# tm8_XP2.net
KiCad netlist of a schematic drawn in EAGLE
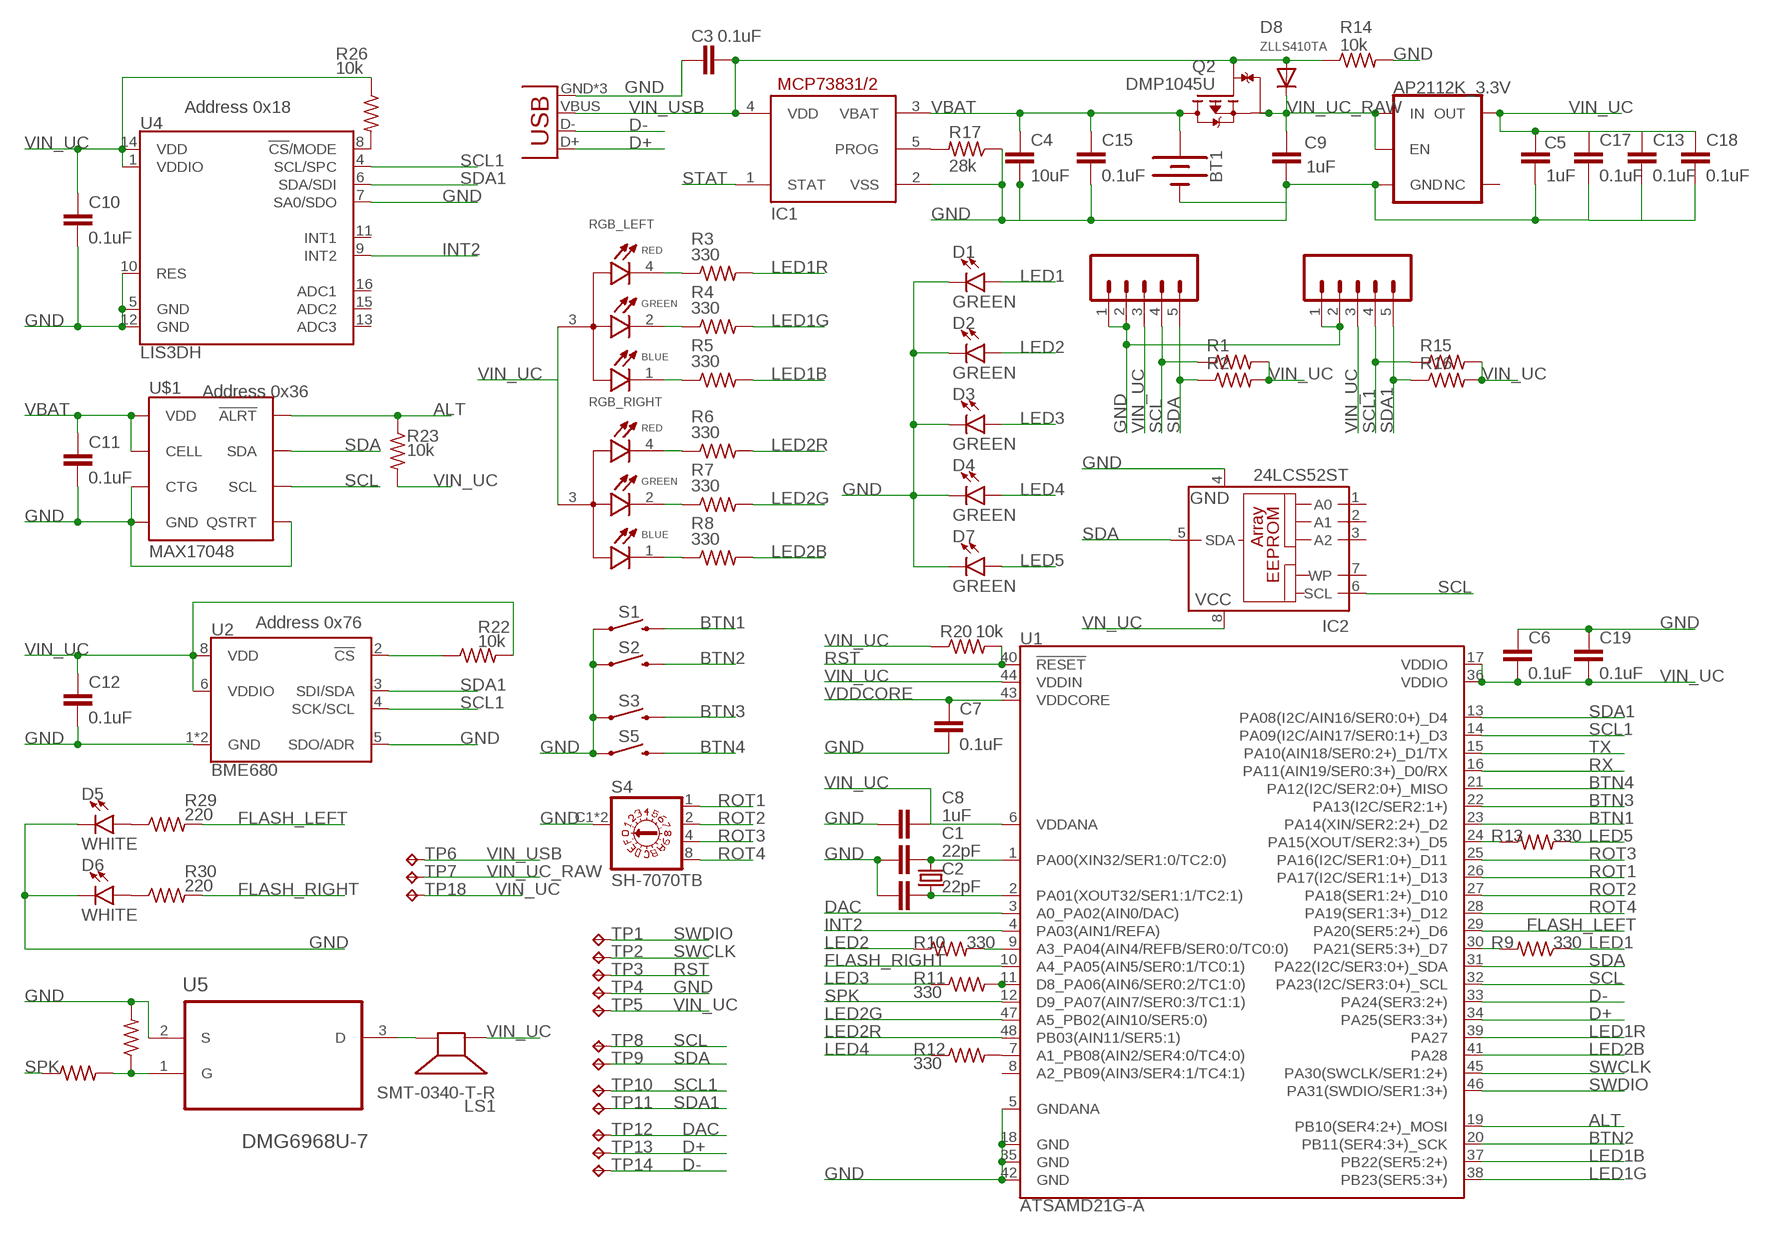
[diagram p0: schematic, sheet 1]

(export (version "E")
  (design (tool "Eeschema 10.0.6"))
  (components
    (comp (ref "AP2112K_3.3V")
      (value "3.3V")
      (footprint "eagle-import:SOT23-5")
      (libsource (lib "eagle-import") (part "V_REG_AP2112K-3.3V"))
    )
    (comp (ref "BT1")
      (value "BATTERY-20MM_SMD_4LEGS_OVERPASTE_INNER")
      (footprint "eagle-import:BATTCON_20MM_4LEGS_OVERPASTE_INNER")
      (libsource (lib "eagle-import") (part "BATTERY-20MM_SMD_4LEGS_OVERPASTE_INNER"))
    )
    (comp (ref "C1")
      (value "22pF")
      (footprint "eagle-import:C0402")
      (libsource (lib "eagle-import") (part "C-EUC0402"))
    )
    (comp (ref "C2")
      (value "22pF")
      (footprint "eagle-import:C0402")
      (libsource (lib "eagle-import") (part "C-EUC0402"))
    )
    (comp (ref "C3")
      (value "0.1uF")
      (footprint "eagle-import:C0402")
      (libsource (lib "eagle-import") (part "C-EUC0402"))
    )
    (comp (ref "C4")
      (value "10uF")
      (footprint "eagle-import:C0402")
      (libsource (lib "eagle-import") (part "C-EUC0402"))
    )
    (comp (ref "C5")
      (value "1uF")
      (footprint "eagle-import:C0402")
      (libsource (lib "eagle-import") (part "C-EUC0402"))
    )
    (comp (ref "C6")
      (value "0.1uF")
      (footprint "eagle-import:C0402")
      (libsource (lib "eagle-import") (part "C-EUC0402"))
    )
    (comp (ref "C7")
      (value "0.1uF")
      (footprint "eagle-import:C0402")
      (libsource (lib "eagle-import") (part "C-EUC0402"))
    )
    (comp (ref "C8")
      (value "1uF")
      (footprint "eagle-import:C0402")
      (libsource (lib "eagle-import") (part "C-EUC0402"))
    )
    (comp (ref "C9")
      (value "1uF")
      (footprint "eagle-import:C0402")
      (libsource (lib "eagle-import") (part "C-EUC0402"))
    )
    (comp (ref "C10")
      (value "0.1uF")
      (footprint "eagle-import:C0402")
      (libsource (lib "eagle-import") (part "C-EUC0402"))
    )
    (comp (ref "C11")
      (value "0.1uF")
      (footprint "eagle-import:C0402")
      (libsource (lib "eagle-import") (part "C-EUC0402"))
    )
    (comp (ref "C12")
      (value "0.1uF")
      (footprint "eagle-import:C0402")
      (libsource (lib "eagle-import") (part "C-EUC0402"))
    )
    (comp (ref "C13")
      (value "0.1uF")
      (footprint "eagle-import:C0402")
      (libsource (lib "eagle-import") (part "C-EUC0402"))
    )
    (comp (ref "C15")
      (value "0.1uF")
      (footprint "eagle-import:C0402")
      (libsource (lib "eagle-import") (part "C-EUC0402"))
    )
    (comp (ref "C17")
      (value "0.1uF")
      (footprint "eagle-import:C0402")
      (libsource (lib "eagle-import") (part "C-EUC0402"))
    )
    (comp (ref "C18")
      (value "0.1uF")
      (footprint "eagle-import:C0402")
      (libsource (lib "eagle-import") (part "C-EUC0402"))
    )
    (comp (ref "C19")
      (value "0.1uF")
      (footprint "eagle-import:C0402")
      (libsource (lib "eagle-import") (part "C-EUC0402"))
    )
    (comp (ref "D1")
      (value "GREEN")
      (footprint "eagle-import:LED-1206")
      (libsource (lib "eagle-import") (part "LED-GREEN1206"))
    )
    (comp (ref "D2")
      (value "GREEN")
      (footprint "eagle-import:LED-1206")
      (libsource (lib "eagle-import") (part "LED-GREEN1206"))
    )
    (comp (ref "D3")
      (value "GREEN")
      (footprint "eagle-import:LED-1206")
      (libsource (lib "eagle-import") (part "LED-GREEN1206"))
    )
    (comp (ref "D4")
      (value "GREEN")
      (footprint "eagle-import:LED-1206")
      (libsource (lib "eagle-import") (part "LED-GREEN1206"))
    )
    (comp (ref "D5")
      (value "WHITE")
      (footprint "eagle-import:LED-1206")
      (libsource (lib "eagle-import") (part "LED-WHITE1206"))
    )
    (comp (ref "D6")
      (value "WHITE")
      (footprint "eagle-import:LED-1206")
      (libsource (lib "eagle-import") (part "LED-WHITE1206"))
    )
    (comp (ref "D7")
      (value "GREEN")
      (footprint "eagle-import:LED-1206")
      (libsource (lib "eagle-import") (part "LED-GREEN1206"))
    )
    (comp (ref "D8")
      (value "ZLLS410TA")
      (footprint "eagle-import:SOD-323F")
      (libsource (lib "eagle-import") (part "DIODESOD-323F"))
    )
    (comp (ref "IC1")
      (value "MCP73831/OT")
      (footprint "eagle-import:SOT23-5L")
      (libsource (lib "eagle-import") (part "MCP73831/OT"))
    )
    (comp (ref "IC2")
      (value "24LCS52ST")
      (footprint "eagle-import:TSSOP8")
      (fields (field (name "MF") "MICROCHIP") (field (name "MPN") "24LCS52T/ST"))
      (libsource (lib "eagle-import") (part "24STLCS52"))
    )
    (comp (ref "JP2")
      (value "USB-MICROB")
      (footprint "eagle-import:USB-MICROB")
      (libsource (lib "eagle-import") (part "USB-MICROB"))
    )
    (comp (ref "LCD1")
      (value "CONN_05VERT_FEMALE_HEADER")
      (footprint "eagle-import:1X05_SMD_VERTICAL_COMBO")
      (libsource (lib "eagle-import") (part "CONN_05VERT_FEMALE_HEADER"))
    )
    (comp (ref "LCD2")
      (value "CONN_05VERT_FEMALE_HEADER")
      (footprint "eagle-import:1X05_SMD_VERTICAL_COMBO")
      (libsource (lib "eagle-import") (part "CONN_05VERT_FEMALE_HEADER"))
    )
    (comp (ref "LS1")
      (value "SMT-0340-T-R")
      (footprint "eagle-import:XDCR_SMT-0340-T-R")
      (fields (field (name "MANUFACTURER") "Pui Audio"))
      (libsource (lib "eagle-import") (part "SMT-0340-T-R"))
    )
    (comp (ref "Q2")
      (value "DMP1045U")
      (footprint "eagle-import:SOT91P240X110-3N")
      (fields (field (name "MF") "Diodes Inc."))
      (libsource (lib "eagle-import") (part "DMP1045U"))
    )
    (comp (ref "R1")
      (value "R-US_R0402")
      (footprint "eagle-import:R0402")
      (libsource (lib "eagle-import") (part "adafruit_25768682_R-US_R0402"))
    )
    (comp (ref "R2")
      (value "R-US_R0402")
      (footprint "eagle-import:R0402")
      (libsource (lib "eagle-import") (part "adafruit_25768682_R-US_R0402"))
    )
    (comp (ref "R3")
      (value "330")
      (footprint "eagle-import:R0402")
      (libsource (lib "eagle-import") (part "rcl_334_R-US_R0402"))
    )
    (comp (ref "R4")
      (value "330")
      (footprint "eagle-import:R0402")
      (libsource (lib "eagle-import") (part "rcl_334_R-US_R0402"))
    )
    (comp (ref "R5")
      (value "330")
      (footprint "eagle-import:R0402")
      (libsource (lib "eagle-import") (part "rcl_334_R-US_R0402"))
    )
    (comp (ref "R6")
      (value "330")
      (footprint "eagle-import:R0402")
      (libsource (lib "eagle-import") (part "rcl_334_R-US_R0402"))
    )
    (comp (ref "R7")
      (value "330")
      (footprint "eagle-import:R0402")
      (libsource (lib "eagle-import") (part "rcl_334_R-US_R0402"))
    )
    (comp (ref "R8")
      (value "330")
      (footprint "eagle-import:R0402")
      (libsource (lib "eagle-import") (part "rcl_334_R-US_R0402"))
    )
    (comp (ref "R9")
      (value "330")
      (footprint "eagle-import:R0402")
      (libsource (lib "eagle-import") (part "rcl_334_R-US_R0402"))
    )
    (comp (ref "R10")
      (value "330")
      (footprint "eagle-import:R0402")
      (libsource (lib "eagle-import") (part "rcl_334_R-US_R0402"))
    )
    (comp (ref "R11")
      (value "330")
      (footprint "eagle-import:R0402")
      (libsource (lib "eagle-import") (part "rcl_334_R-US_R0402"))
    )
    (comp (ref "R12")
      (value "330")
      (footprint "eagle-import:R0402")
      (libsource (lib "eagle-import") (part "rcl_334_R-US_R0402"))
    )
    (comp (ref "R13")
      (value "330")
      (footprint "eagle-import:R0402")
      (libsource (lib "eagle-import") (part "rcl_334_R-US_R0402"))
    )
    (comp (ref "R14")
      (value "10k")
      (footprint "eagle-import:R0402")
      (libsource (lib "eagle-import") (part "R-US_R0402"))
    )
    (comp (ref "R15")
      (value "R-US_R0402")
      (footprint "eagle-import:R0402")
      (libsource (lib "eagle-import") (part "adafruit_25768682_R-US_R0402"))
    )
    (comp (ref "R16")
      (value "R-US_R0402")
      (footprint "eagle-import:R0402")
      (libsource (lib "eagle-import") (part "adafruit_25768682_R-US_R0402"))
    )
    (comp (ref "R17")
      (value "28k")
      (footprint "eagle-import:R0402")
      (libsource (lib "eagle-import") (part "adafruit_25768682_R-US_R0402"))
    )
    (comp (ref "R18")
      (value "220")
      (footprint "eagle-import:R0402")
      (libsource (lib "eagle-import") (part "rcl_334_R-US_R0402"))
    )
    (comp (ref "R19")
      (value "220")
      (footprint "eagle-import:R0402")
      (libsource (lib "eagle-import") (part "rcl_334_R-US_R0402"))
    )
    (comp (ref "R20")
      (value "10k")
      (footprint "eagle-import:R0402")
      (libsource (lib "eagle-import") (part "adafruit_25768682_R-US_R0402"))
    )
    (comp (ref "R22")
      (value "10k")
      (footprint "eagle-import:R0402")
      (libsource (lib "eagle-import") (part "rcl_334_R-US_R0402"))
    )
    (comp (ref "R23")
      (value "10k")
      (footprint "eagle-import:R0402")
      (libsource (lib "eagle-import") (part "rcl_334_R-US_R0402"))
    )
    (comp (ref "R26")
      (value "10k")
      (footprint "eagle-import:R0402")
      (libsource (lib "eagle-import") (part "rcl_334_R-US_R0402"))
    )
    (comp (ref "R29")
      (value "220")
      (footprint "eagle-import:R0402")
      (libsource (lib "eagle-import") (part "rcl_334_R-US_R0402"))
    )
    (comp (ref "R30")
      (value "220")
      (footprint "eagle-import:R0402")
      (libsource (lib "eagle-import") (part "rcl_334_R-US_R0402"))
    )
    (comp (ref "RGB_LEFT")
      (value "EAST1616RGBA3")
      (footprint "eagle-import:LED_EAST1616RGBA3")
      (fields (field (name "MF") "Everlight Electronics"))
      (libsource (lib "eagle-import") (part "EAST1616RGBA3"))
    )
    (comp (ref "RGB_RIGHT")
      (value "EAST1616RGBA3")
      (footprint "eagle-import:LED_EAST1616RGBA3")
      (fields (field (name "MF") "Everlight Electronics"))
      (libsource (lib "eagle-import") (part "EAST1616RGBA3"))
    )
    (comp (ref "S1")
      (value "MOMENTARY-SWITCH-SPST-SMD-6.0X3.5MM")
      (footprint "eagle-import:TACTILE_SWITCH_SMD_6.0X3.5MM")
      (libsource (lib "eagle-import") (part "MOMENTARY-SWITCH-SPST-SMD-6.0X3.5MM"))
    )
    (comp (ref "S2")
      (value "MOMENTARY-SWITCH-SPST-SMD-6.0X3.5MM")
      (footprint "eagle-import:TACTILE_SWITCH_SMD_6.0X3.5MM")
      (libsource (lib "eagle-import") (part "MOMENTARY-SWITCH-SPST-SMD-6.0X3.5MM"))
    )
    (comp (ref "S3")
      (value "MOMENTARY-SWITCH-SPST-SMD-6.0X3.5MM")
      (footprint "eagle-import:TACTILE_SWITCH_SMD_6.0X3.5MM")
      (libsource (lib "eagle-import") (part "MOMENTARY-SWITCH-SPST-SMD-6.0X3.5MM"))
    )
    (comp (ref "S4")
      (value "SH-7070TB")
      (footprint "eagle-import:SH-7070B")
      (fields (field (name "MF") "Nidec Copal"))
      (libsource (lib "eagle-import") (part "SH-7070TB"))
    )
    (comp (ref "S5")
      (value "MOMENTARY-SWITCH-SPST-SMD-6.0X3.5MM")
      (footprint "eagle-import:TACTILE_SWITCH_SMD_6.0X3.5MM")
      (libsource (lib "eagle-import") (part "MOMENTARY-SWITCH-SPST-SMD-6.0X3.5MM"))
    )
    (comp (ref "TP1")
      (value "TPTP14R")
      (footprint "eagle-import:TP14R")
      (libsource (lib "eagle-import") (part "TPTP14R"))
    )
    (comp (ref "TP2")
      (value "TPTP14R")
      (footprint "eagle-import:TP14R")
      (libsource (lib "eagle-import") (part "TPTP14R"))
    )
    (comp (ref "TP3")
      (value "TPTP14R")
      (footprint "eagle-import:TP14R")
      (libsource (lib "eagle-import") (part "TPTP14R"))
    )
    (comp (ref "TP4")
      (value "TPTP14R")
      (footprint "eagle-import:TP14R")
      (libsource (lib "eagle-import") (part "TPTP14R"))
    )
    (comp (ref "TP5")
      (value "TPTP14R")
      (footprint "eagle-import:TP14R")
      (libsource (lib "eagle-import") (part "TPTP14R"))
    )
    (comp (ref "TP6")
      (value "TPTP14R")
      (footprint "eagle-import:TP14R")
      (libsource (lib "eagle-import") (part "TPTP14R"))
    )
    (comp (ref "TP7")
      (value "TPTP14R")
      (footprint "eagle-import:TP14R")
      (libsource (lib "eagle-import") (part "TPTP14R"))
    )
    (comp (ref "TP8")
      (value "TPTP14R")
      (footprint "eagle-import:TP14R")
      (libsource (lib "eagle-import") (part "TPTP14R"))
    )
    (comp (ref "TP9")
      (value "TPTP14R")
      (footprint "eagle-import:TP14R")
      (libsource (lib "eagle-import") (part "TPTP14R"))
    )
    (comp (ref "TP10")
      (value "TPTP14R")
      (footprint "eagle-import:TP14R")
      (libsource (lib "eagle-import") (part "TPTP14R"))
    )
    (comp (ref "TP11")
      (value "TPTP14R")
      (footprint "eagle-import:TP14R")
      (libsource (lib "eagle-import") (part "TPTP14R"))
    )
    (comp (ref "TP12")
      (value "TPTP14R")
      (footprint "eagle-import:TP14R")
      (libsource (lib "eagle-import") (part "TPTP14R"))
    )
    (comp (ref "TP13")
      (value "TPTP14R")
      (footprint "eagle-import:TP14R")
      (libsource (lib "eagle-import") (part "TPTP14R"))
    )
    (comp (ref "TP14")
      (value "TPTP14R")
      (footprint "eagle-import:TP14R")
      (libsource (lib "eagle-import") (part "TPTP14R"))
    )
    (comp (ref "TP18")
      (value "TPTP14R")
      (footprint "eagle-import:TP14R")
      (libsource (lib "eagle-import") (part "TPTP14R"))
    )
    (comp (ref "U$1")
      (value "MAX17048")
      (footprint "eagle-import:DFN-8")
      (libsource (lib "eagle-import") (part "MAX17048DFN8"))
    )
    (comp (ref "U1")
      (value "ATSAMD21G-A")
      (footprint "eagle-import:TQFP-48")
      (libsource (lib "eagle-import") (part "ATSAMD21G-A"))
    )
    (comp (ref "U2")
      (value "BME680")
      (footprint "eagle-import:LGA3.0X3.0")
      (libsource (lib "eagle-import") (part "BME680-LGA"))
    )
    (comp (ref "U4")
      (value "LIS3DH")
      (footprint "eagle-import:LGA-16-3X3")
      (libsource (lib "eagle-import") (part "LIS3DH"))
    )
    (comp (ref "U5")
      (value "DMG6968U-7")
      (footprint "eagle-import:SOT95P240X110-3N")
      (fields (field (name "MF") "Diodes Inc."))
      (libsource (lib "eagle-import") (part "DMG6968U-7"))
    )
    (comp (ref "Y1")
      (value "32.768kHz")
      (footprint "eagle-import:CRYSTAL-SMD-3.2X1.5MM")
      (libsource (lib "eagle-import") (part "CRYSTAL-32.768KHZSMD-3.2X1.5"))
    )
  )
  (nets
    (net (code "1") (name "/ALT") (class "Default")
      (node (ref "R23") (pin "1") (pinfunction "1_1") (pintype "passive"))
      (node (ref "U$1") (pin "P$5") (pinfunction "~{ALRT}_P$5") (pintype "bidirectional"))
      (node (ref "U1") (pin "19") (pinfunction "PB10(SER4:2+)_MOSI_19") (pintype "bidirectional"))
    )
    (net (code "2") (name "/BTN1") (class "Default")
      (node (ref "S1") (pin "2") (pinfunction "2_2") (pintype "passive"))
      (node (ref "U1") (pin "23") (pinfunction "PA14(XIN/SER2:2+)_D2_23") (pintype "bidirectional"))
    )
    (net (code "3") (name "/BTN2") (class "Default")
      (node (ref "S2") (pin "2") (pinfunction "2_2") (pintype "passive"))
      (node (ref "U1") (pin "20") (pinfunction "PB11(SER4:3+)_SCK_20") (pintype "bidirectional"))
    )
    (net (code "4") (name "/BTN3") (class "Default")
      (node (ref "S3") (pin "2") (pinfunction "2_2") (pintype "passive"))
      (node (ref "U1") (pin "22") (pinfunction "PA13(I2C/SER2:1+)_22") (pintype "bidirectional"))
    )
    (net (code "5") (name "/BTN4") (class "Default")
      (node (ref "S5") (pin "2") (pinfunction "2_2") (pintype "passive"))
      (node (ref "U1") (pin "21") (pinfunction "PA12(I2C/SER2:0+)_MISO_21") (pintype "bidirectional"))
    )
    (net (code "6") (name "/D+") (class "Default")
      (node (ref "JP2") (pin "D+") (pinfunction "D+_D+") (pintype "bidirectional"))
      (node (ref "TP13") (pin "TP") (pinfunction "TP_TP") (pintype "input"))
      (node (ref "U1") (pin "34") (pinfunction "PA25(SER3:3+)_34") (pintype "bidirectional"))
    )
    (net (code "7") (name "/D-") (class "Default")
      (node (ref "JP2") (pin "D-") (pinfunction "D-_D-") (pintype "bidirectional"))
      (node (ref "TP14") (pin "TP") (pinfunction "TP_TP") (pintype "input"))
      (node (ref "U1") (pin "33") (pinfunction "PA24(SER3:2+)_33") (pintype "bidirectional"))
    )
    (net (code "8") (name "/DAC") (class "Default")
      (node (ref "TP12") (pin "TP") (pinfunction "TP_TP") (pintype "input"))
      (node (ref "U1") (pin "3") (pinfunction "A0_PA02(AIN0/DAC)_3") (pintype "bidirectional"))
    )
    (net (code "9") (name "/FLASH_LEFT") (class "Default")
      (node (ref "R29") (pin "2") (pinfunction "2_2") (pintype "passive"))
      (node (ref "U1") (pin "29") (pinfunction "PA20(SER5:2+)_D6_29") (pintype "bidirectional"))
    )
    (net (code "10") (name "/FLASH_RIGHT") (class "Default")
      (node (ref "R30") (pin "2") (pinfunction "2_2") (pintype "passive"))
      (node (ref "U1") (pin "10") (pinfunction "A4_PA05(AIN5/SER0:1/TC0:1)_10") (pintype "bidirectional"))
    )
    (net (code "11") (name "/GND") (class "Default")
      (node (ref "AP2112K_3.3V") (pin "2") (pinfunction "GND_2") (pintype "input"))
      (node (ref "BT1") (pin "2") (pinfunction "-_2") (pintype "power_in"))
      (node (ref "C1") (pin "1") (pinfunction "1_1") (pintype "passive"))
      (node (ref "C10") (pin "2") (pinfunction "2_2") (pintype "passive"))
      (node (ref "C11") (pin "2") (pinfunction "2_2") (pintype "passive"))
      (node (ref "C12") (pin "2") (pinfunction "2_2") (pintype "passive"))
      (node (ref "C13") (pin "2") (pinfunction "2_2") (pintype "passive"))
      (node (ref "C15") (pin "2") (pinfunction "2_2") (pintype "passive"))
      (node (ref "C17") (pin "2") (pinfunction "2_2") (pintype "passive"))
      (node (ref "C18") (pin "2") (pinfunction "2_2") (pintype "passive"))
      (node (ref "C19") (pin "1") (pinfunction "1_1") (pintype "passive"))
      (node (ref "C2") (pin "1") (pinfunction "1_1") (pintype "passive"))
      (node (ref "C3") (pin "1") (pinfunction "1_1") (pintype "passive"))
      (node (ref "C4") (pin "2") (pinfunction "2_2") (pintype "passive"))
      (node (ref "C5") (pin "2") (pinfunction "2_2") (pintype "passive"))
      (node (ref "C6") (pin "1") (pinfunction "1_1") (pintype "passive"))
      (node (ref "C7") (pin "2") (pinfunction "2_2") (pintype "passive"))
      (node (ref "C8") (pin "1") (pinfunction "1_1") (pintype "passive"))
      (node (ref "C9") (pin "2") (pinfunction "2_2") (pintype "passive"))
      (node (ref "D1") (pin "C") (pinfunction "C_C") (pintype "passive"))
      (node (ref "D2") (pin "C") (pinfunction "C_C") (pintype "passive"))
      (node (ref "D3") (pin "C") (pinfunction "C_C") (pintype "passive"))
      (node (ref "D4") (pin "C") (pinfunction "C_C") (pintype "passive"))
      (node (ref "D5") (pin "C") (pinfunction "C_C") (pintype "passive"))
      (node (ref "D6") (pin "C") (pinfunction "C_C") (pintype "passive"))
      (node (ref "D7") (pin "C") (pinfunction "C_C") (pintype "passive"))
      (node (ref "IC1") (pin "2") (pinfunction "VSS_2") (pintype "power_in"))
      (node (ref "IC2") (pin "4") (pinfunction "GND_4") (pintype "power_in"))
      (node (ref "JP2") (pin "GND") (pinfunction "GND_GND") (pintype "bidirectional"))
      (node (ref "JP2") (pin "MT1") (pinfunction "GND_MT1") (pintype "bidirectional"))
      (node (ref "JP2") (pin "MT2") (pinfunction "GND_MT2") (pintype "bidirectional"))
      (node (ref "LCD1") (pin "1") (pinfunction "1_1") (pintype "passive"))
      (node (ref "LCD1") (pin "2") (pinfunction "2_2") (pintype "passive"))
      (node (ref "LCD2") (pin "1") (pinfunction "1_1") (pintype "passive"))
      (node (ref "LCD2") (pin "2") (pinfunction "2_2") (pintype "passive"))
      (node (ref "R14") (pin "2") (pinfunction "2_2") (pintype "passive"))
      (node (ref "R17") (pin "1") (pinfunction "1_1") (pintype "passive"))
      (node (ref "R19") (pin "2") (pinfunction "2_2") (pintype "passive"))
      (node (ref "S1") (pin "1") (pinfunction "1_1") (pintype "passive"))
      (node (ref "S2") (pin "1") (pinfunction "1_1") (pintype "passive"))
      (node (ref "S3") (pin "1") (pinfunction "1_1") (pintype "passive"))
      (node (ref "S4") (pin "C1") (pinfunction "C_C1") (pintype "passive"))
      (node (ref "S4") (pin "C2") (pinfunction "C_C2") (pintype "passive"))
      (node (ref "S5") (pin "1") (pinfunction "1_1") (pintype "passive"))
      (node (ref "TP4") (pin "TP") (pinfunction "TP_TP") (pintype "input"))
      (node (ref "U$1") (pin "P$1") (pinfunction "CTG_P$1") (pintype "input"))
      (node (ref "U$1") (pin "P$4") (pinfunction "GND_P$4") (pintype "bidirectional"))
      (node (ref "U$1") (pin "P$6") (pinfunction "QSTRT_P$6") (pintype "bidirectional"))
      (node (ref "U$1") (pin "P$9") (pinfunction "GND_P$9") (pintype "bidirectional"))
      (node (ref "U1") (pin "18") (pinfunction "GND_18") (pintype "bidirectional"))
      (node (ref "U1") (pin "35") (pinfunction "GND_35") (pintype "bidirectional"))
      (node (ref "U1") (pin "42") (pinfunction "GND_42") (pintype "bidirectional"))
      (node (ref "U1") (pin "5") (pinfunction "GNDANA_5") (pintype "bidirectional"))
      (node (ref "U2") (pin "1") (pinfunction "GND_1") (pintype "bidirectional"))
      (node (ref "U2") (pin "5") (pinfunction "SDO/ADR_5") (pintype "bidirectional"))
      (node (ref "U2") (pin "7") (pinfunction "GND_7") (pintype "bidirectional"))
      (node (ref "U4") (pin "10") (pinfunction "RES_10") (pintype "bidirectional"))
      (node (ref "U4") (pin "12") (pinfunction "GND_12") (pintype "bidirectional"))
      (node (ref "U4") (pin "5") (pinfunction "GND_5") (pintype "bidirectional"))
      (node (ref "U4") (pin "7") (pinfunction "SA0/SDO_7") (pintype "bidirectional"))
      (node (ref "U5") (pin "2") (pinfunction "S_2") (pintype "passive"))
    )
    (net (code "12") (name "/INT2") (class "Default")
      (node (ref "U1") (pin "4") (pinfunction "PA03(AIN1/REFA)_4") (pintype "bidirectional"))
      (node (ref "U4") (pin "9") (pinfunction "INT2_9") (pintype "bidirectional"))
    )
    (net (code "13") (name "/LED1") (class "Default")
      (node (ref "D1") (pin "A") (pinfunction "A_A") (pintype "passive"))
      (node (ref "R9") (pin "1") (pinfunction "1_1") (pintype "passive"))
    )
    (net (code "14") (name "/LED1B") (class "Default")
      (node (ref "R5") (pin "2") (pinfunction "2_2") (pintype "passive"))
      (node (ref "U1") (pin "37") (pinfunction "PB22(SER5:2+)_37") (pintype "bidirectional"))
    )
    (net (code "15") (name "/LED1G") (class "Default")
      (node (ref "R4") (pin "2") (pinfunction "2_2") (pintype "passive"))
      (node (ref "U1") (pin "38") (pinfunction "PB23(SER5:3+)_38") (pintype "bidirectional"))
    )
    (net (code "16") (name "/LED1R") (class "Default")
      (node (ref "R3") (pin "2") (pinfunction "2_2") (pintype "passive"))
      (node (ref "U1") (pin "39") (pinfunction "PA27_39") (pintype "bidirectional"))
    )
    (net (code "17") (name "/LED2") (class "Default")
      (node (ref "D2") (pin "A") (pinfunction "A_A") (pintype "passive"))
      (node (ref "R10") (pin "1") (pinfunction "1_1") (pintype "passive"))
    )
    (net (code "18") (name "/LED2B") (class "Default")
      (node (ref "R8") (pin "2") (pinfunction "2_2") (pintype "passive"))
      (node (ref "U1") (pin "41") (pinfunction "PA28_41") (pintype "bidirectional"))
    )
    (net (code "19") (name "/LED2G") (class "Default")
      (node (ref "R7") (pin "2") (pinfunction "2_2") (pintype "passive"))
      (node (ref "U1") (pin "47") (pinfunction "A5_PB02(AIN10/SER5:0)_47") (pintype "bidirectional"))
    )
    (net (code "20") (name "/LED2R") (class "Default")
      (node (ref "R6") (pin "2") (pinfunction "2_2") (pintype "passive"))
      (node (ref "U1") (pin "48") (pinfunction "PB03(AIN11/SER5:1)_48") (pintype "bidirectional"))
    )
    (net (code "21") (name "/LED3") (class "Default")
      (node (ref "D3") (pin "A") (pinfunction "A_A") (pintype "passive"))
      (node (ref "R11") (pin "1") (pinfunction "1_1") (pintype "passive"))
    )
    (net (code "22") (name "/LED4") (class "Default")
      (node (ref "D4") (pin "A") (pinfunction "A_A") (pintype "passive"))
      (node (ref "R12") (pin "1") (pinfunction "1_1") (pintype "passive"))
    )
    (net (code "23") (name "/LED5") (class "Default")
      (node (ref "D7") (pin "A") (pinfunction "A_A") (pintype "passive"))
      (node (ref "R13") (pin "2") (pinfunction "2_2") (pintype "passive"))
    )
    (net (code "24") (name "/ROT1") (class "Default")
      (node (ref "S4") (pin "1") (pinfunction "1_1") (pintype "passive"))
      (node (ref "U1") (pin "26") (pinfunction "PA17(I2C/SER1:1+)_D13_26") (pintype "bidirectional"))
    )
    (net (code "25") (name "/ROT2") (class "Default")
      (node (ref "S4") (pin "2") (pinfunction "2_2") (pintype "passive"))
      (node (ref "U1") (pin "27") (pinfunction "PA18(SER1:2+)_D10_27") (pintype "bidirectional"))
    )
    (net (code "26") (name "/ROT3") (class "Default")
      (node (ref "S4") (pin "4") (pinfunction "4_4") (pintype "passive"))
      (node (ref "U1") (pin "25") (pinfunction "PA16(I2C/SER1:0+)_D11_25") (pintype "bidirectional"))
    )
    (net (code "27") (name "/ROT4") (class "Default")
      (node (ref "S4") (pin "8") (pinfunction "8_8") (pintype "passive"))
      (node (ref "U1") (pin "28") (pinfunction "PA19(SER1:3+)_D12_28") (pintype "bidirectional"))
    )
    (net (code "28") (name "/RST") (class "Default")
      (node (ref "R20") (pin "2") (pinfunction "2_2") (pintype "passive"))
      (node (ref "TP3") (pin "TP") (pinfunction "TP_TP") (pintype "input"))
      (node (ref "U1") (pin "40") (pinfunction "~{RESET}_40") (pintype "bidirectional"))
    )
    (net (code "29") (name "/RX") (class "Default")
      (node (ref "U1") (pin "16") (pinfunction "PA11(AIN19/SER0:3+)_D0/RX_16") (pintype "bidirectional"))
    )
    (net (code "30") (name "/SCL") (class "Default")
      (node (ref "IC2") (pin "6") (pinfunction "SCL_6") (pintype "input"))
      (node (ref "LCD1") (pin "4") (pinfunction "4_4") (pintype "passive"))
      (node (ref "R1") (pin "1") (pinfunction "1_1") (pintype "passive"))
      (node (ref "TP8") (pin "TP") (pinfunction "TP_TP") (pintype "input"))
      (node (ref "U$1") (pin "P$7") (pinfunction "SCL_P$7") (pintype "output"))
      (node (ref "U1") (pin "32") (pinfunction "PA23(I2C/SER3:0+)_SCL_32") (pintype "bidirectional"))
    )
    (net (code "31") (name "/SCL1") (class "Default")
      (node (ref "LCD2") (pin "4") (pinfunction "4_4") (pintype "passive"))
      (node (ref "R15") (pin "1") (pinfunction "1_1") (pintype "passive"))
      (node (ref "TP10") (pin "TP") (pinfunction "TP_TP") (pintype "input"))
      (node (ref "U1") (pin "14") (pinfunction "PA09(I2C/AIN17/SER0:1+)_D3_14") (pintype "bidirectional"))
      (node (ref "U2") (pin "4") (pinfunction "SCK/SCL_4") (pintype "bidirectional"))
      (node (ref "U4") (pin "4") (pinfunction "SCL/SPC_4") (pintype "bidirectional"))
    )
    (net (code "32") (name "/SDA") (class "Default")
      (node (ref "IC2") (pin "5") (pinfunction "SDA_5") (pintype "bidirectional"))
      (node (ref "LCD1") (pin "5") (pinfunction "5_5") (pintype "passive"))
      (node (ref "R2") (pin "1") (pinfunction "1_1") (pintype "passive"))
      (node (ref "TP9") (pin "TP") (pinfunction "TP_TP") (pintype "input"))
      (node (ref "U$1") (pin "P$8") (pinfunction "SDA_P$8") (pintype "input"))
      (node (ref "U1") (pin "31") (pinfunction "PA22(I2C/SER3:0+)_SDA_31") (pintype "bidirectional"))
    )
    (net (code "33") (name "/SDA1") (class "Default")
      (node (ref "LCD2") (pin "5") (pinfunction "5_5") (pintype "passive"))
      (node (ref "R16") (pin "1") (pinfunction "1_1") (pintype "passive"))
      (node (ref "TP11") (pin "TP") (pinfunction "TP_TP") (pintype "input"))
      (node (ref "U1") (pin "13") (pinfunction "PA08(I2C/AIN16/SER0:0+)_D4_13") (pintype "bidirectional"))
      (node (ref "U2") (pin "3") (pinfunction "SDI/SDA_3") (pintype "bidirectional"))
      (node (ref "U4") (pin "6") (pinfunction "SDA/SDI_6") (pintype "bidirectional"))
    )
    (net (code "34") (name "/SPK") (class "Default")
      (node (ref "R18") (pin "1") (pinfunction "1_1") (pintype "passive"))
      (node (ref "U1") (pin "12") (pinfunction "D9_PA07(AIN7/SER0:3/TC1:1)_12") (pintype "bidirectional"))
    )
    (net (code "35") (name "/STAT") (class "Default")
      (node (ref "IC1") (pin "1") (pinfunction "STAT_1") (pintype "output"))
    )
    (net (code "36") (name "/SWCLK") (class "Default")
      (node (ref "TP2") (pin "TP") (pinfunction "TP_TP") (pintype "input"))
      (node (ref "U1") (pin "45") (pinfunction "PA30(SWCLK/SER1:2+)_45") (pintype "bidirectional"))
    )
    (net (code "37") (name "/SWDIO") (class "Default")
      (node (ref "TP1") (pin "TP") (pinfunction "TP_TP") (pintype "input"))
      (node (ref "U1") (pin "46") (pinfunction "PA31(SWDIO/SER1:3+)_46") (pintype "bidirectional"))
    )
    (net (code "38") (name "/TX") (class "Default")
      (node (ref "U1") (pin "15") (pinfunction "PA10(AIN18/SER0:2+)_D1/TX_15") (pintype "bidirectional"))
    )
    (net (code "39") (name "/VBAT") (class "Default")
      (node (ref "BT1") (pin "1") (pinfunction "+_1") (pintype "power_in"))
      (node (ref "C11") (pin "1") (pinfunction "1_1") (pintype "passive"))
      (node (ref "C15") (pin "1") (pinfunction "1_1") (pintype "passive"))
      (node (ref "C4") (pin "1") (pinfunction "1_1") (pintype "passive"))
      (node (ref "IC1") (pin "3") (pinfunction "VBAT_3") (pintype "bidirectional"))
      (node (ref "Q2") (pin "3") (pinfunction "D_3") (pintype "passive"))
      (node (ref "U$1") (pin "P$2") (pinfunction "CELL_P$2") (pintype "input"))
      (node (ref "U$1") (pin "P$3") (pinfunction "VDD_P$3") (pintype "bidirectional"))
    )
    (net (code "40") (name "/VDDCORE") (class "Default")
      (node (ref "C7") (pin "1") (pinfunction "1_1") (pintype "passive"))
      (node (ref "U1") (pin "43") (pinfunction "VDDCORE_43") (pintype "bidirectional"))
    )
    (net (code "41") (name "/VIN_UC") (class "Default")
      (node (ref "AP2112K_3.3V") (pin "5") (pinfunction "OUT_5") (pintype "passive"))
      (node (ref "C10") (pin "1") (pinfunction "1_1") (pintype "passive"))
      (node (ref "C12") (pin "1") (pinfunction "1_1") (pintype "passive"))
      (node (ref "C13") (pin "1") (pinfunction "1_1") (pintype "passive"))
      (node (ref "C17") (pin "1") (pinfunction "1_1") (pintype "passive"))
      (node (ref "C18") (pin "1") (pinfunction "1_1") (pintype "passive"))
      (node (ref "C19") (pin "2") (pinfunction "2_2") (pintype "passive"))
      (node (ref "C5") (pin "1") (pinfunction "1_1") (pintype "passive"))
      (node (ref "C6") (pin "2") (pinfunction "2_2") (pintype "passive"))
      (node (ref "C8") (pin "2") (pinfunction "2_2") (pintype "passive"))
      (node (ref "LCD1") (pin "3") (pinfunction "3_3") (pintype "passive"))
      (node (ref "LCD2") (pin "3") (pinfunction "3_3") (pintype "passive"))
      (node (ref "LS1") (pin "P") (pinfunction "P_P") (pintype "passive"))
      (node (ref "R1") (pin "2") (pinfunction "2_2") (pintype "passive"))
      (node (ref "R15") (pin "2") (pinfunction "2_2") (pintype "passive"))
      (node (ref "R16") (pin "2") (pinfunction "2_2") (pintype "passive"))
      (node (ref "R2") (pin "2") (pinfunction "2_2") (pintype "passive"))
      (node (ref "R20") (pin "1") (pinfunction "1_1") (pintype "passive"))
      (node (ref "R22") (pin "2") (pinfunction "2_2") (pintype "passive"))
      (node (ref "R23") (pin "2") (pinfunction "2_2") (pintype "passive"))
      (node (ref "R26") (pin "1") (pinfunction "1_1") (pintype "passive"))
      (node (ref "RGB_LEFT") (pin "3") (pinfunction "A_3") (pintype "passive"))
      (node (ref "RGB_RIGHT") (pin "3") (pinfunction "A_3") (pintype "passive"))
      (node (ref "TP18") (pin "TP") (pinfunction "TP_TP") (pintype "input"))
      (node (ref "TP5") (pin "TP") (pinfunction "TP_TP") (pintype "input"))
      (node (ref "U1") (pin "17") (pinfunction "VDDIO_17") (pintype "bidirectional"))
      (node (ref "U1") (pin "36") (pinfunction "VDDIO_36") (pintype "bidirectional"))
      (node (ref "U1") (pin "44") (pinfunction "VDDIN_44") (pintype "bidirectional"))
      (node (ref "U1") (pin "6") (pinfunction "VDDANA_6") (pintype "bidirectional"))
      (node (ref "U2") (pin "6") (pinfunction "VDDIO_6") (pintype "bidirectional"))
      (node (ref "U2") (pin "8") (pinfunction "VDD_8") (pintype "bidirectional"))
      (node (ref "U4") (pin "1") (pinfunction "VDDIO_1") (pintype "bidirectional"))
      (node (ref "U4") (pin "14") (pinfunction "VDD_14") (pintype "bidirectional"))
    )
    (net (code "42") (name "/VIN_UC_RAW") (class "Default")
      (node (ref "AP2112K_3.3V") (pin "1") (pinfunction "IN_1") (pintype "input"))
      (node (ref "AP2112K_3.3V") (pin "3") (pinfunction "EN_3") (pintype "input"))
      (node (ref "C9") (pin "1") (pinfunction "1_1") (pintype "passive"))
      (node (ref "D8") (pin "C") (pinfunction "C_C") (pintype "passive"))
      (node (ref "Q2") (pin "2") (pinfunction "S_2") (pintype "passive"))
      (node (ref "TP7") (pin "TP") (pinfunction "TP_TP") (pintype "input"))
    )
    (net (code "43") (name "/VIN_USB") (class "Default")
      (node (ref "C3") (pin "2") (pinfunction "2_2") (pintype "passive"))
      (node (ref "D8") (pin "A") (pinfunction "A_A") (pintype "passive"))
      (node (ref "IC1") (pin "4") (pinfunction "VDD_4") (pintype "power_in"))
      (node (ref "JP2") (pin "VBUS") (pinfunction "VBUS_VBUS") (pintype "bidirectional"))
      (node (ref "Q2") (pin "1") (pinfunction "G_1") (pintype "passive"))
      (node (ref "R14") (pin "1") (pinfunction "1_1") (pintype "passive"))
      (node (ref "TP6") (pin "TP") (pinfunction "TP_TP") (pintype "input"))
    )
    (net (code "44") (name "/VN_UC") (class "Default")
      (node (ref "IC2") (pin "8") (pinfunction "VCC_8") (pintype "power_in"))
    )
    (net (code "45") (name "Net-(D5-PadA)") (class "Default")
      (node (ref "D5") (pin "A") (pinfunction "A_A") (pintype "passive"))
      (node (ref "R29") (pin "1") (pinfunction "1_1") (pintype "passive"))
    )
    (net (code "46") (name "Net-(D6-PadA)") (class "Default")
      (node (ref "D6") (pin "A") (pinfunction "A_A") (pintype "passive"))
      (node (ref "R30") (pin "1") (pinfunction "1_1") (pintype "passive"))
    )
    (net (code "47") (name "Net-(IC1-PROG)") (class "Default")
      (node (ref "IC1") (pin "5") (pinfunction "PROG_5") (pintype "input"))
      (node (ref "R17") (pin "2") (pinfunction "2_2") (pintype "passive"))
    )
    (net (code "48") (name "Net-(RGB_LEFT-B_C)") (class "Default")
      (node (ref "R5") (pin "1") (pinfunction "1_1") (pintype "passive"))
      (node (ref "RGB_LEFT") (pin "1") (pinfunction "B_C_1") (pintype "passive"))
    )
    (net (code "49") (name "Net-(RGB_LEFT-G_C)") (class "Default")
      (node (ref "R4") (pin "1") (pinfunction "1_1") (pintype "passive"))
      (node (ref "RGB_LEFT") (pin "2") (pinfunction "G_C_2") (pintype "passive"))
    )
    (net (code "50") (name "Net-(RGB_LEFT-R_C)") (class "Default")
      (node (ref "R3") (pin "1") (pinfunction "1_1") (pintype "passive"))
      (node (ref "RGB_LEFT") (pin "4") (pinfunction "R_C_4") (pintype "passive"))
    )
    (net (code "51") (name "Net-(RGB_RIGHT-B_C)") (class "Default")
      (node (ref "R8") (pin "1") (pinfunction "1_1") (pintype "passive"))
      (node (ref "RGB_RIGHT") (pin "1") (pinfunction "B_C_1") (pintype "passive"))
    )
    (net (code "52") (name "Net-(RGB_RIGHT-G_C)") (class "Default")
      (node (ref "R7") (pin "1") (pinfunction "1_1") (pintype "passive"))
      (node (ref "RGB_RIGHT") (pin "2") (pinfunction "G_C_2") (pintype "passive"))
    )
    (net (code "53") (name "Net-(RGB_RIGHT-R_C)") (class "Default")
      (node (ref "R6") (pin "1") (pinfunction "1_1") (pintype "passive"))
      (node (ref "RGB_RIGHT") (pin "4") (pinfunction "R_C_4") (pintype "passive"))
    )
    (net (code "54") (name "Net-(U1-A1_PB08(AIN2{slash}SER4:0{slash}TC4:0))") (class "Default")
      (node (ref "R12") (pin "2") (pinfunction "2_2") (pintype "passive"))
      (node (ref "U1") (pin "7") (pinfunction "A1_PB08(AIN2/SER4:0/TC4:0)_7") (pintype "bidirectional"))
    )
    (net (code "55") (name "Net-(U1-A3_PA04(AIN4{slash}REFB{slash}SER0:0{slash}TC0:0))") (class "Default")
      (node (ref "R10") (pin "2") (pinfunction "2_2") (pintype "passive"))
      (node (ref "U1") (pin "9") (pinfunction "A3_PA04(AIN4/REFB/SER0:0/TC0:0)_9") (pintype "bidirectional"))
    )
    (net (code "56") (name "Net-(U1-D8_PA06(AIN6{slash}SER0:2{slash}TC1:0))") (class "Default")
      (node (ref "R11") (pin "2") (pinfunction "2_2") (pintype "passive"))
      (node (ref "U1") (pin "11") (pinfunction "D8_PA06(AIN6/SER0:2/TC1:0)_11") (pintype "bidirectional"))
    )
    (net (code "57") (name "Net-(U1-PA00(XIN32{slash}SER1:0{slash}TC2:0))") (class "Default")
      (node (ref "C1") (pin "2") (pinfunction "2_2") (pintype "passive"))
      (node (ref "U1") (pin "1") (pinfunction "PA00(XIN32/SER1:0/TC2:0)_1") (pintype "bidirectional"))
      (node (ref "Y1") (pin "P$2") (pinfunction "2_P$2") (pintype "passive"))
    )
    (net (code "58") (name "Net-(U1-PA01(XOUT32{slash}SER1:1{slash}TC2:1))") (class "Default")
      (node (ref "C2") (pin "2") (pinfunction "2_2") (pintype "passive"))
      (node (ref "U1") (pin "2") (pinfunction "PA01(XOUT32/SER1:1/TC2:1)_2") (pintype "bidirectional"))
      (node (ref "Y1") (pin "P$1") (pinfunction "1_P$1") (pintype "passive"))
    )
    (net (code "59") (name "Net-(U1-PA15(XOUT{slash}SER2:3+)_D5)") (class "Default")
      (node (ref "R13") (pin "1") (pinfunction "1_1") (pintype "passive"))
      (node (ref "U1") (pin "24") (pinfunction "PA15(XOUT/SER2:3+)_D5_24") (pintype "bidirectional"))
    )
    (net (code "60") (name "Net-(U1-PA21(SER5:3+)_D7)") (class "Default")
      (node (ref "R9") (pin "2") (pinfunction "2_2") (pintype "passive"))
      (node (ref "U1") (pin "30") (pinfunction "PA21(SER5:3+)_D7_30") (pintype "bidirectional"))
    )
    (net (code "61") (name "Net-(U2-~{CS})") (class "Default")
      (node (ref "R22") (pin "1") (pinfunction "1_1") (pintype "passive"))
      (node (ref "U2") (pin "2") (pinfunction "~{CS}_2") (pintype "bidirectional"))
    )
    (net (code "62") (name "Net-(U4-~{CS}{slash}MODE)") (class "Default")
      (node (ref "R26") (pin "2") (pinfunction "2_2") (pintype "passive"))
      (node (ref "U4") (pin "8") (pinfunction "~{CS}/MODE_8") (pintype "bidirectional"))
    )
    (net (code "63") (name "Net-(U5-D)") (class "Default")
      (node (ref "LS1") (pin "N") (pinfunction "N_N") (pintype "passive"))
      (node (ref "U5") (pin "3") (pinfunction "D_3") (pintype "output"))
    )
    (net (code "64") (name "Net-(U5-G)") (class "Default")
      (node (ref "R18") (pin "2") (pinfunction "2_2") (pintype "passive"))
      (node (ref "R19") (pin "1") (pinfunction "1_1") (pintype "passive"))
      (node (ref "U5") (pin "1") (pinfunction "G_1") (pintype "power_in"))
    )
    (net (code "65") (name "unconnected-(AP2112K_3.3V-NC-Pad4)") (class "Default")
      (node (ref "AP2112K_3.3V") (pin "4") (pinfunction "NC_4") (pintype "no_connect"))
    )
    (net (code "66") (name "unconnected-(IC2-A0-Pad1)") (class "Default")
      (node (ref "IC2") (pin "1") (pinfunction "A0_1") (pintype "input"))
    )
    (net (code "67") (name "unconnected-(IC2-A1-Pad2)") (class "Default")
      (node (ref "IC2") (pin "2") (pinfunction "A1_2") (pintype "input"))
    )
    (net (code "68") (name "unconnected-(IC2-A2-Pad3)") (class "Default")
      (node (ref "IC2") (pin "3") (pinfunction "A2_3") (pintype "input"))
    )
    (net (code "69") (name "unconnected-(IC2-WP-Pad7)") (class "Default")
      (node (ref "IC2") (pin "7") (pinfunction "WP_7") (pintype "input"))
    )
    (net (code "70") (name "unconnected-(U1-A2_PB09(AIN3{slash}SER4:1{slash}TC4:1)-Pad8)") (class "Default")
      (node (ref "U1") (pin "8") (pinfunction "A2_PB09(AIN3/SER4:1/TC4:1)_8") (pintype "bidirectional"))
    )
    (net (code "71") (name "unconnected-(U4-ADC1-Pad16)") (class "Default")
      (node (ref "U4") (pin "16") (pinfunction "ADC1_16") (pintype "bidirectional"))
    )
    (net (code "72") (name "unconnected-(U4-ADC2-Pad15)") (class "Default")
      (node (ref "U4") (pin "15") (pinfunction "ADC2_15") (pintype "bidirectional"))
    )
    (net (code "73") (name "unconnected-(U4-ADC3-Pad13)") (class "Default")
      (node (ref "U4") (pin "13") (pinfunction "ADC3_13") (pintype "bidirectional"))
    )
    (net (code "74") (name "unconnected-(U4-INT1-Pad11)") (class "Default")
      (node (ref "U4") (pin "11") (pinfunction "INT1_11") (pintype "bidirectional"))
    )
  )
)
